# Phase_5.net
KiCad netlist of a schematic drawn in Altium Designer
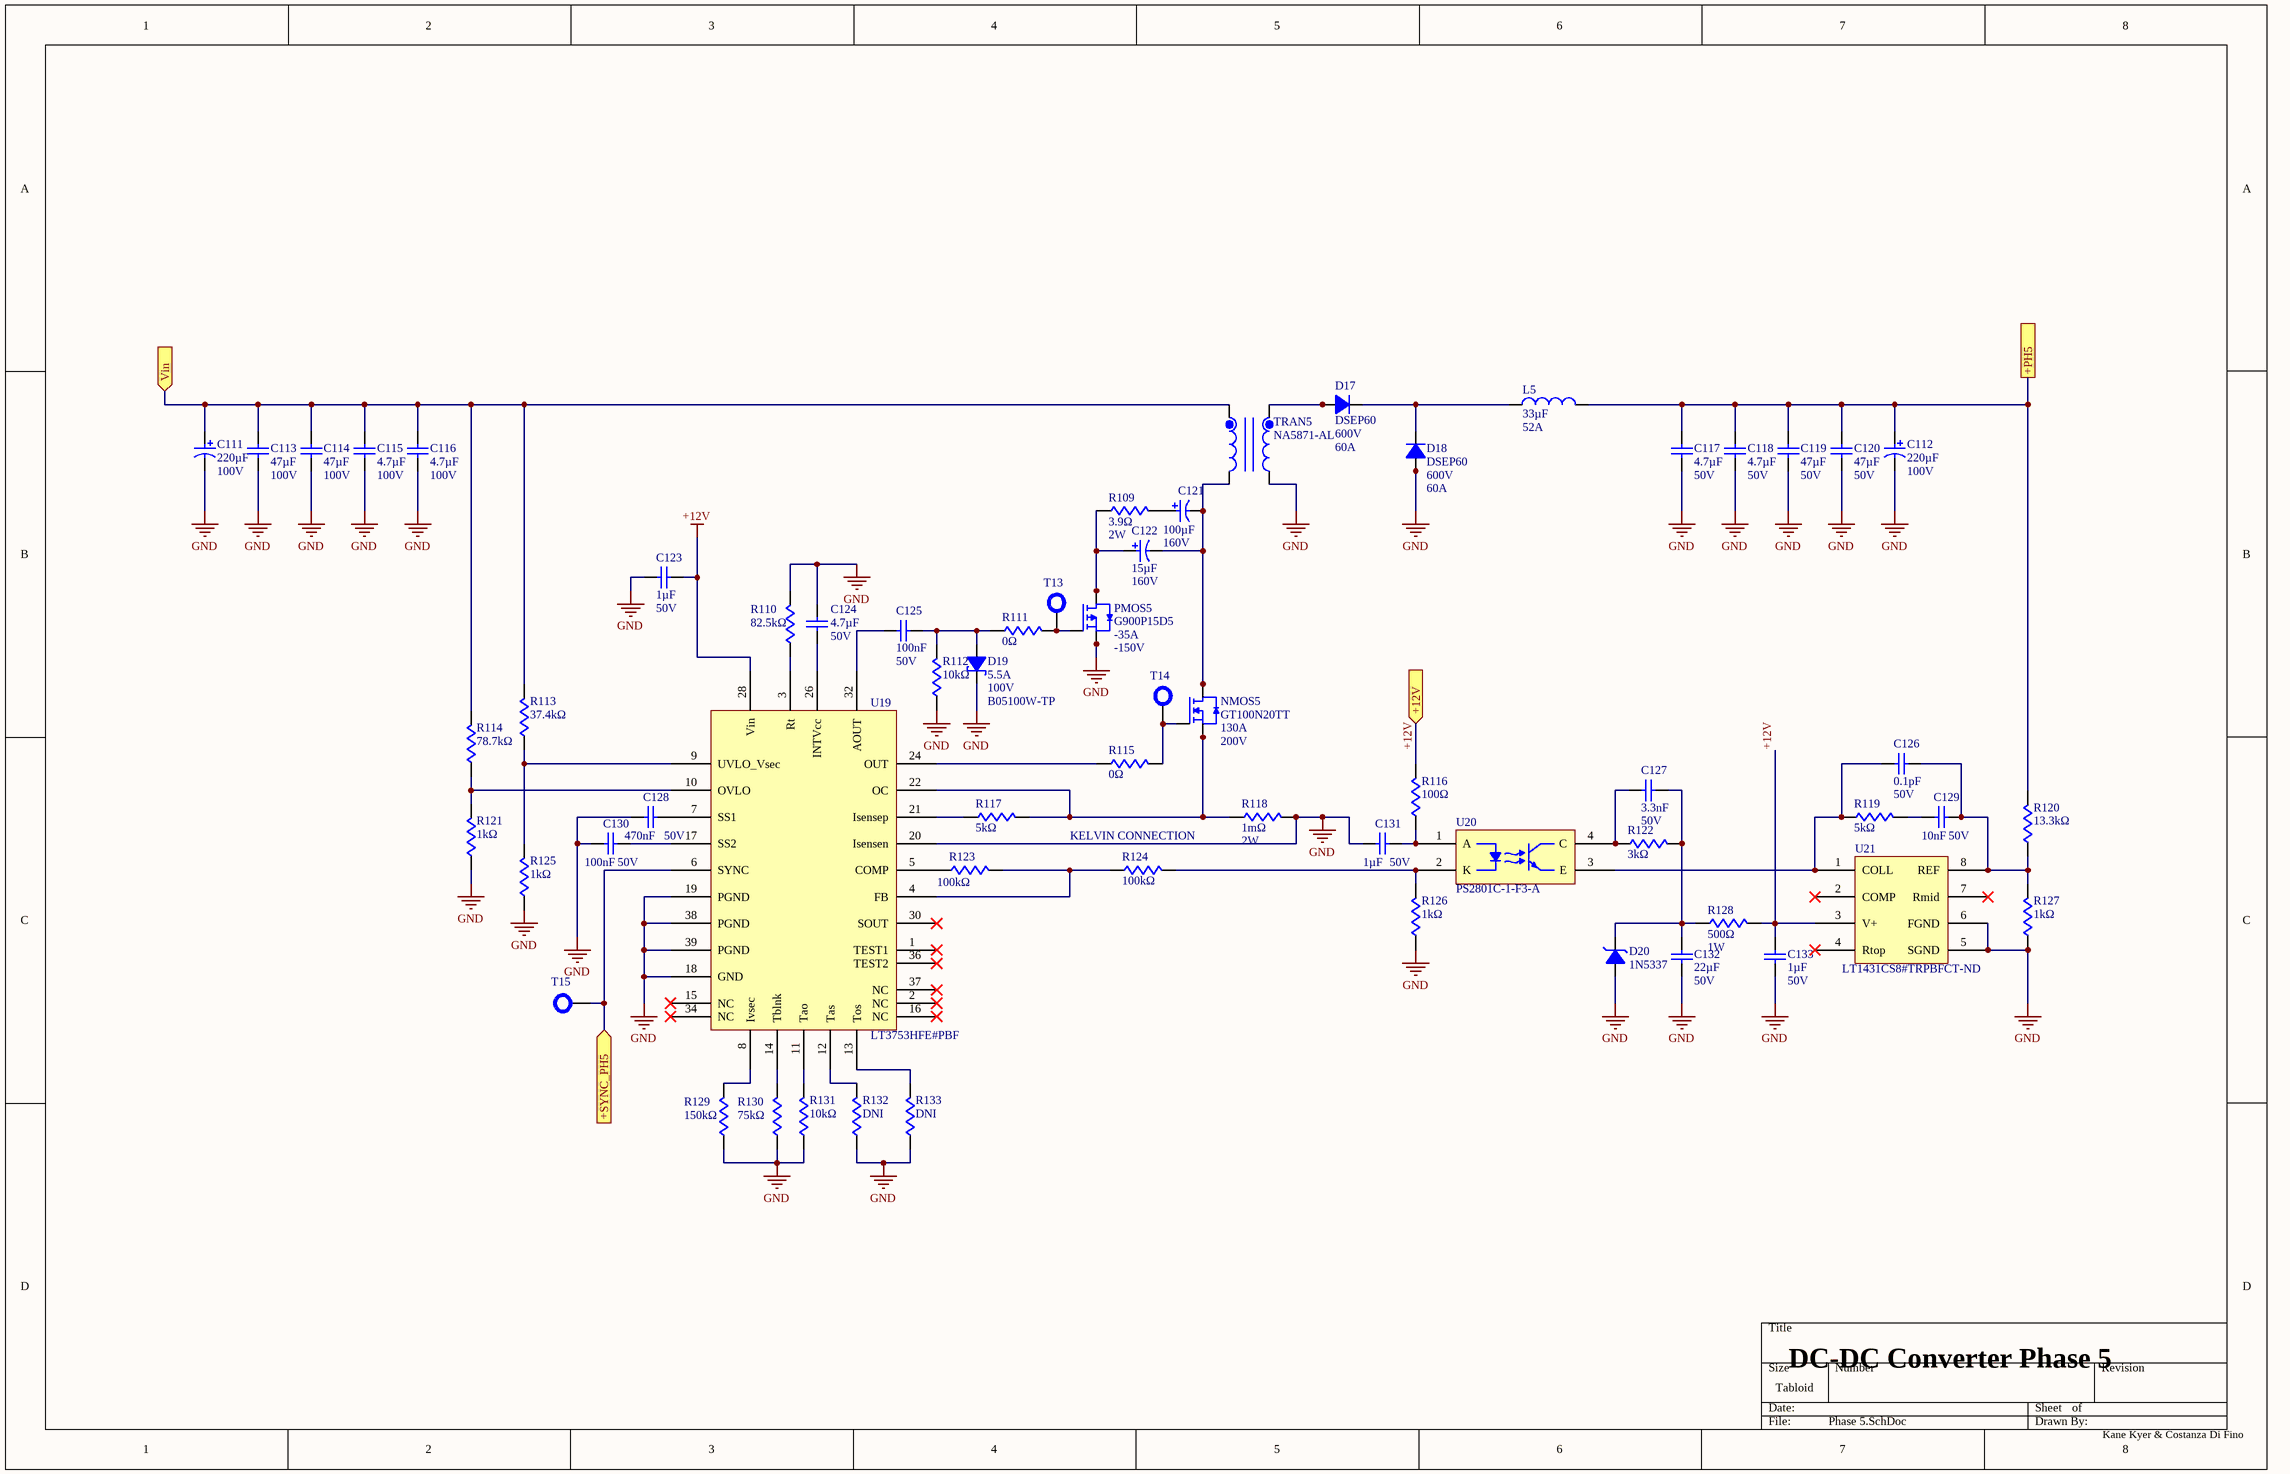
[diagram p0: Phase 5.SchDoc]

(export (version "E")
  (design (tool "Eeschema 10.0.6"))
  (components
    (comp (ref "C111")
      (value "220µF")
      (footprint "C_AEC")
      (description "Radial Can - SMD ALUMINUM ELECTROLYTIC CAPACITOR AFK 100V 220muF ±20% 0.709Dia 18.00mm")
      (fields
        (field (name "MANUFACTURER") "Cornell Dubilier")
        (field (name "MANUFACTURER PART NUMBER") "AFK227M2AR44T-F")
        (field (name "VOLTAGE RATING") "100V")
      )
      (libsource (lib "library") (part "AFK227M2AR44T-F"))
    )
    (comp (ref "C112")
      (value "220µF")
      (footprint "C_AEC")
      (description "Radial Can - SMD ALUMINUM ELECTROLYTIC CAPACITOR AFK 100V 220muF ±20% 0.709Dia 18.00mm")
      (fields
        (field (name "MANUFACTURER") "Cornell Dubilier")
        (field (name "MANUFACTURER PART NUMBER") "AFK227M2AR44T-F")
        (field (name "VOLTAGE RATING") "100V")
      )
      (libsource (lib "library") (part "AFK227M2AR44T-F"))
    )
    (comp (ref "C113")
      (value "47µF")
      (footprint "C_CAA573")
      (description "Multilayer Ceramic Chip Capacitors, Capacitance=47μF, LxWxT: 6.0x7.5x6.4mm")
      (fields
        (field (name "MANUFACTURER") "TDK")
        (field (name "MANUFACTURER PART NUMBER") "CAA573X7S2A476M640LH")
        (field (name "VOLTAGE RATING") "100V")
      )
      (libsource (lib "library") (part "CAA573X7S2A476M640LH"))
    )
    (comp (ref "C114")
      (value "47µF")
      (footprint "C_CAA573")
      (description "Multilayer Ceramic Chip Capacitors, Capacitance=47μF, LxWxT: 6.0x7.5x6.4mm")
      (fields
        (field (name "MANUFACTURER") "TDK")
        (field (name "MANUFACTURER PART NUMBER") "CAA573X7S2A476M640LH")
        (field (name "VOLTAGE RATING") "100V")
      )
      (libsource (lib "library") (part "CAA573X7S2A476M640LH"))
    )
    (comp (ref "C115")
      (value "4.7µF")
      (footprint "C_1210")
      (fields
        (field (name "MANUFACTURER") "Cal-Chip Electronics")
        (field (name "MANUFACTURER PART NUMBER") "GMC32X7S475K100NT")
        (field (name "VOLTAGE RATING (DC)") "100V")
      )
      (libsource (lib "library") (part "GMC32X7S475K100NT"))
    )
    (comp (ref "C116")
      (value "4.7µF")
      (footprint "C_1210")
      (fields
        (field (name "MANUFACTURER") "Cal-Chip Electronics")
        (field (name "MANUFACTURER PART NUMBER") "GMC32X7S475K100NT")
        (field (name "VOLTAGE RATING (DC)") "100V")
      )
      (libsource (lib "library") (part "GMC32X7S475K100NT"))
    )
    (comp (ref "C117")
      (value "4.7µF")
      (footprint "C_1206")
      (fields
        (field (name "MANUFACTURER") "Cal-Chip Electronics")
        (field (name "MANUFACTURER PART NUMBER") "GMC31X7R475K50NT")
        (field (name "VOLTAGE RATING (DC)") "50V")
      )
      (libsource (lib "library") (part "GMC31X7R475K50NT"))
    )
    (comp (ref "C118")
      (value "4.7µF")
      (footprint "C_1206")
      (fields
        (field (name "MANUFACTURER") "Cal-Chip Electronics")
        (field (name "MANUFACTURER PART NUMBER") "GMC31X7R475K50NT")
        (field (name "VOLTAGE RATING (DC)") "50V")
      )
      (libsource (lib "library") (part "GMC31X7R475K50NT"))
    )
    (comp (ref "C119")
      (value "47µF")
      (footprint "C_CKG57N")
      (fields
        (field (name "MANUFACTURER") "TDK")
        (field (name "MANUFACTURER PART NUMBER") "CKG57NX7R1H476M500JJ")
        (field (name "VOLTAGE RATING (DC)") "50V")
      )
      (libsource (lib "library") (part "CKG57NX7R1H476M500JJ"))
    )
    (comp (ref "C120")
      (value "47µF")
      (footprint "C_CKG57N")
      (fields
        (field (name "MANUFACTURER") "TDK")
        (field (name "MANUFACTURER PART NUMBER") "CKG57NX7R1H476M500JJ")
        (field (name "VOLTAGE RATING (DC)") "50V")
      )
      (libsource (lib "library") (part "CKG57NX7R1H476M500JJ"))
    )
    (comp (ref "C121")
      (value "100µF")
      (footprint "UUJ2C101MNJ1MS")
      (description "Aluminum Electrolytic Capacitors 100 F 160 V Radial, SMD 5000 Hrs 105C")
      (fields
        (field (name "MANUFACTURER") "Nichicon")
        (field (name "MANUFACTURER PART NUMBER") "UUJ2C101MNJ1MS")
        (field (name "VOLTAGE RATING (DC)") "160V")
      )
      (libsource (lib "library") (part "UUJ2C101MNJ1MS"))
    )
    (comp (ref "C122")
      (value "15µF")
      (footprint "ULT2C150MNL1GS")
      (description "Radial Can - SMD ALUMINUM ELECTROLYTIC CAPACITOR ULT 160V 15muF ±20% 0.315Dia 8.00mm")
      (fields
        (field (name "MANUFACTURER") "Nichicon")
        (field (name "MANUFACTURER PART NUMBER") "ULT2C150MNL1GS")
        (field (name "VOLTAGE") "160V")
      )
      (libsource (lib "library") (part "ULT2C150MNL1GS"))
    )
    (comp (ref "C123")
      (value "1µF")
      (footprint "C_0805")
      (description "50V 1uF X7R ±10% 0805 Multilayer Ceramic Capacitors MLCC - SMD/SMT ROHS")
      (fields
        (field (name "MANUFACTURER") "Samsung Electro-Mechanics")
        (field (name "MANUFACTURER PART NUMBER") "CL21B105KBFNNNE")
        (field (name "VOLTAGE") "50V")
      )
      (libsource (lib "library") (part "CL21B105KBFNNNE"))
    )
    (comp (ref "C124")
      (value "4.7µF")
      (footprint "C_1206")
      (fields
        (field (name "MANUFACTURER") "Cal-Chip Electronics")
        (field (name "MANUFACTURER PART NUMBER") "GMC31X7R475K50NT")
        (field (name "VOLTAGE RATING (DC)") "50V")
      )
      (libsource (lib "library") (part "GMC31X7R475K50NT"))
    )
    (comp (ref "C125")
      (value "100nF")
      (footprint "C_0603")
      (description "50V 100nF X7R ±10% 0603 Multilayer Ceramic Capacitors MLCC - SMD/SMT ROHS")
      (fields
        (field (name "MANUFACTURER") "KEMET")
        (field (name "MANUFACTURER PART NUMBER") "C0603C104K5RACTU")
        (field (name "VOLTAGE RATING") "50V")
      )
      (libsource (lib "library") (part "C0603C104K5RACTU"))
    )
    (comp (ref "C126")
      (value "0.1pF")
      (footprint "C_0402")
      (description "Multilayer Ceramic Capacitor, 0.1 pF, 50 V, ± 0.05pF, C0G (NP0), 0402 [1005 Metric]")
      (fields
        (field (name "MANUFACTURER") "Murata")
        (field (name "MANUFACTURER PART NUMBER") "GJM1555C1HR10WB01D")
        (field (name "VOLTAGE RATING") "50V")
      )
      (libsource (lib "library") (part "GJM1555C1HR10WB01D"))
    )
    (comp (ref "C127")
      (value "3.3nF")
      (footprint "C_0603")
      (description "50V 3.3nF C0G ±1% 0603 Multilayer Ceramic Capacitors MLCC - SMD/SMT ROHS")
      (fields
        (field (name "MANUFACTURER") "Murata")
        (field (name "MANUFACTURER PART NUMBER") "GCM1885C1H332FA16D")
        (field (name "VOLTAGE RATING") "50V")
      )
      (libsource (lib "library") (part "GCM1885C1H332FA16D"))
    )
    (comp (ref "C128")
      (value "470nF")
      (footprint "C_0402")
      (description "50V 470nF X5R ±10% 0402 Multilayer Ceramic Capacitors MLCC - SMD/SMT ROHS")
      (fields
        (field (name "MANUFACTURER") "Murata")
        (field (name "MANUFACTURER PART NUMBER") "GRM155R61H474KE11D")
        (field (name "VOLTAGE RATING") "50V")
      )
      (libsource (lib "library") (part "GRM155R61H474KE11D"))
    )
    (comp (ref "C129")
      (value "10nF")
      (footprint "C_0603")
      (description "Capacitor, Multilayer, Ceramic, 50V, 10%, X7R, 15% Tc, 0.01Uf, Surface Mount, 0603")
      (fields
        (field (name "MANUFACTURER") "KEMET")
        (field (name "MANUFACTURER PART NUMBER") "C0603C103K5RACTU")
        (field (name "VOLTAGE RATING") "50V")
      )
      (libsource (lib "library") (part "C0603C103K5RACTU"))
    )
    (comp (ref "C130")
      (value "100nF")
      (footprint "C_0603")
      (description "50V 100nF X7R ±10% 0603 Multilayer Ceramic Capacitors MLCC - SMD/SMT ROHS")
      (fields
        (field (name "MANUFACTURER") "KEMET")
        (field (name "MANUFACTURER PART NUMBER") "C0603C104K5RACTU")
        (field (name "VOLTAGE RATING") "50V")
      )
      (libsource (lib "library") (part "C0603C104K5RACTU"))
    )
    (comp (ref "C131")
      (value "1µF")
      (footprint "C_0805")
      (description "50V 1uF X7R ±10% 0805 Multilayer Ceramic Capacitors MLCC - SMD/SMT ROHS")
      (fields
        (field (name "MANUFACTURER") "Samsung Electro-Mechanics")
        (field (name "MANUFACTURER PART NUMBER") "CL21B105KBFNNNE")
        (field (name "VOLTAGE") "50V")
      )
      (libsource (lib "library") (part "CL21B105KBFNNNE"))
    )
    (comp (ref "C132")
      (value "22µF")
      (footprint "C_2220")
      (fields
        (field (name "MANUFACTURER") "Cal-Chip Electronics")
        (field (name "MANUFACTURER PART NUMBER") "GMC55X7R226M50NT")
        (field (name "VOLTAGE RATING (DC)") "50V")
      )
      (libsource (lib "library") (part "GMC55X7R226M50NT"))
    )
    (comp (ref "C133")
      (value "1µF")
      (footprint "C_0805")
      (description "50V 1uF X7R ±10% 0805 Multilayer Ceramic Capacitors MLCC - SMD/SMT ROHS")
      (fields
        (field (name "MANUFACTURER") "Samsung Electro-Mechanics")
        (field (name "MANUFACTURER PART NUMBER") "CL21B105KBFNNNE")
        (field (name "VOLTAGE") "50V")
      )
      (libsource (lib "library") (part "CL21B105KBFNNNE"))
    )
    (comp (ref "D17")
      (value "DSEP60")
      (footprint "D_DSEP60")
      (description "Power Diode Discretes-FRED TO-")
      (fields
        (field (name "MANUFACTURER") "IXYS")
        (field (name "MANUFACTURER PART NUMBER") "DSEP60-06AZ-TRL")
        (field (name "VR") "600V")
        (field (name "IO") "60A")
      )
      (libsource (lib "library") (part "DSEP60-06AZ-TRL"))
    )
    (comp (ref "D18")
      (value "DSEP60")
      (footprint "D_DSEP60")
      (description "Power Diode Discretes-FRED TO-")
      (fields
        (field (name "MANUFACTURER") "IXYS")
        (field (name "MANUFACTURER PART NUMBER") "DSEP60-06AZ-TRL")
        (field (name "VR") "600V")
        (field (name "IO") "60A")
      )
      (libsource (lib "library") (part "DSEP60-06AZ-TRL"))
    )
    (comp (ref "D19")
      (value "B05100W-TP")
      (footprint "D_B05100W")
      (description "Rectifier Diode, Schottky, 1 Phase, 1 Element, 0.5A, 100V V(RRM), Silicon")
      (fields
        (field (name "MANUFACTURER") "MCC")
        (field (name "MAX FORWARD SURGE CURRENT (IFSM)") "5.5A")
        (field (name "MIN BREAKDOWN VOLTAGE") "100V")
        (field (name "MANUFACTURER PART NUMBER") "B05100W-TP")
      )
      (libsource (lib "library") (part "B05100W-TP"))
    )
    (comp (ref "D20")
      (value "1N5337BRLG")
      (footprint "D_1N5337")
      (description "Zener Diode Single 4.7V 5% 2Ohm 5000mW 2-Pin Case 017AA-01 T/R / DIODE ZENER 4.7V 5W AXIAL")
      (fields
        (field (name "MANUFACTURER") "onsemi")
        (field (name "TOLERANCE") "5%")
        (field (name "SUPPLIER PART NUMBER") "1N5337")
      )
      (libsource (lib "library") (part "1N5337BRLG"))
    )
    (comp (ref "L5")
      (value "33µF")
      (footprint "CPEX4141L-330MC")
      (description "Fixed Ind 33UH 52A 1.88 Mohm Th")
      (fields
        (field (name "MANUFACTURER") "Codaca")
        (field (name "MANUFACTURER PART NUMBER") "CPEX4141L-330MC")
        (field (name "IRMS") "52A")
      )
      (libsource (lib "library") (part "CPEX4141L-330MC"))
    )
    (comp (ref "NMOS5")
      (value "GT100N20TT")
      (footprint "GT100N20TT")
      (description "Mosfet N-ch 200V 130A 280W Tolt")
      (fields
        (field (name "MANUFACTURER") "GoFord")
        (field (name "MANUFACTURER PART NUMBER") "GT100N20TT")
        (field (name "ID") "130A")
        (field (name "VDS") "200V")
      )
      (libsource (lib "library") (part "GT100N20TT"))
    )
    (comp (ref "PMOS5")
      (value "G900P15D5")
      (footprint "G900P15")
      (description "P-150V, -60A, RD(max) Less Than 80mOhm at -10V, VTH -1V to -4V, DFN5x6-8L")
      (fields
        (field (name "MANUFACTURER") "GoFord")
        (field (name "MANUFACTURER PART NUMBER") "G900P15D5")
        (field (name "ID") "-35A")
        (field (name "VDS") "-150V")
      )
      (libsource (lib "library") (part "G900P15D5"))
    )
    (comp (ref "R109")
      (value "3.9Ω")
      (footprint "R_SM2W")
      (description "SM Series 3.9 Ohm ±5 % 2 W ±200 ppm/°C Surface Mount Wirewound Resistor")
      (fields
        (field (name "MANUFACTURER") "TE Connectivity")
        (field (name "MANUFACTURER PART NUMBER") "SMW23R9JT")
        (field (name "POWER RATING") "2W")
      )
      (libsource (lib "library") (part "SMW23R9JT"))
    )
    (comp (ref "R110")
      (value "82.5kΩ")
      (footprint "R_0805")
      (description "Res Thick Film 0805 82.5K Ohm 1% 1/8W ±100ppm/°C Molded SMD SMD Paper T/R")
      (fields
        (field (name "MANUFACTURER") "Stackpole Electronics")
        (field (name "MANUFACTURER PART NUMBER") "RMCF0805FT82K5")
      )
      (libsource (lib "library") (part "RMCF0805FT82K5"))
    )
    (comp (ref "R111")
      (value "0Ω")
      (footprint "R_0805")
      (description "Zero Ohm Resistor, Jumper, 0805 [2012 Metric], Thick Film, 125 mW, 2.5 A, Surface Mount Device")
      (fields
        (field (name "MANUFACTURER") "Vishay")
        (field (name "MANUFACTURER PART NUMBER") "CRCW08050000Z0EA")
      )
      (libsource (lib "library") (part "CRCW08050000Z0EA"))
    )
    (comp (ref "R112")
      (value "10kΩ")
      (footprint "R_0402")
      (description "Fixed Resistor, Metal Glaze/thick Film, 0.0625W, 10000ohm, 50V, 1% +/-Tol, Surface Mount, 0402")
      (fields
        (field (name "MANUFACTURER") "Cal-Chip Electronics")
        (field (name "MANUFACTURER PART NUMBER") "RM04F1002CT")
      )
      (libsource (lib "library") (part "RM04F1002CT"))
    )
    (comp (ref "R113")
      (value "37.4kΩ")
      (footprint "R_0603")
      (description "100mW Thick Film Resistors 75V ±100ppm/℃ ±1% 37.4kΩ 0603 Chip Resistor - Surface Mount ROHS")
      (fields
        (field (name "MANUFACTURER") "Yageo Group")
        (field (name "MANUFACTURER PART NUMBER") "RC0603FR-0737K4L")
      )
      (libsource (lib "library") (part "RC0603FR-0737K4L"))
    )
    (comp (ref "R114")
      (value "78.7kΩ")
      (footprint "R_0603")
      (description "Res Thick Film 0603 78.7K Ohm 1% 0.1W(1/10W) ±100ppm/C Pad SMD T/R")
      (fields
        (field (name "MANUFACTURER") "Yageo Group")
        (field (name "MANUFACTURER PART NUMBER") "RC0603FR-0778K7L")
      )
      (libsource (lib "library") (part "RC0603FR-0778K7L"))
    )
    (comp (ref "R115")
      (value "0Ω")
      (footprint "R_0805")
      (description "Zero Ohm Resistor, Jumper, 0805 [2012 Metric], Thick Film, 125 mW, 2.5 A, Surface Mount Device")
      (fields
        (field (name "MANUFACTURER") "Vishay")
        (field (name "MANUFACTURER PART NUMBER") "CRCW08050000Z0EA")
      )
      (libsource (lib "library") (part "CRCW08050000Z0EA"))
    )
    (comp (ref "R116")
      (value "100Ω")
      (footprint "R_0603")
      (description "Yageo RC0603FR-07100RL 0603 SMD Resistor 100 Ohm thin film chip resistor")
      (fields
        (field (name "MANUFACTURER") "Yageo Group")
        (field (name "MANUFACTURER PART NUMBER") "RC0603FR-07100RL")
      )
      (libsource (lib "library") (part "RC0603FR-07100RL"))
    )
    (comp (ref "R117")
      (value "5kΩ")
      (footprint "R_0402")
      (description "Res Thin Film 0402 5K Ohm 0.1% 0.05W(1/20W) +/-25ppm/C Sulfur Resistant Pad SMD Medical T/R")
      (fields
        (field (name "MANUFACTURER") "Vishay")
        (field (name "MANUFACTURER PART NUMBER") "PNM0402E5001BST1")
      )
      (libsource (lib "library") (part "PNM0402E5001BST1"))
    )
    (comp (ref "R118")
      (value "1mΩ")
      (footprint "R_2512")
      (description "Res Thick Film 2512 1m Ohm 1% 2W ±75ppm/°C Molded SMD Embossed T/R")
      (fields
        (field (name "MANUFACTURER") "Bourns")
        (field (name "MANUFACTURER PART NUMBER") "CRE2512-FZ-R001E-2")
        (field (name "POWER RATING") "2W")
      )
      (libsource (lib "library") (part "CRE2512-FZ-R001E-2"))
    )
    (comp (ref "R119")
      (value "5kΩ")
      (footprint "R_0402")
      (description "Res Thin Film 0402 5K Ohm 0.1% 0.05W(1/20W) +/-25ppm/C Sulfur Resistant Pad SMD Medical T/R")
      (fields
        (field (name "MANUFACTURER") "Vishay")
        (field (name "MANUFACTURER PART NUMBER") "PNM0402E5001BST1")
      )
      (libsource (lib "library") (part "PNM0402E5001BST1"))
    )
    (comp (ref "R120")
      (value "13.3kΩ")
      (footprint "R_0603")
      (description "Res Thick Film 0603 13.3K Ohm 1% 0.1W(1/10W) ±100ppm/C Pad SMD Automotive T/R")
      (fields
        (field (name "MANUFACTURER") "Stackpole Electronics")
        (field (name "MANUFACTURER PART NUMBER") "RMCF0603FT13K3")
      )
      (libsource (lib "library") (part "RMCF0603FT13K3"))
    )
    (comp (ref "R121")
      (value "1kΩ")
      (footprint "R_0402")
      (description "62.5mW Thick Film Resistors ±100ppm/℃ ±1% 1kΩ 0402 Chip Resistor - Surface Mount ROHS")
      (fields
        (field (name "MANUFACTURER") "Cal-Chip Electronics")
        (field (name "MANUFACTURER PART NUMBER") "RM04F1001CT")
      )
      (libsource (lib "library") (part "RM04F1001CT"))
    )
    (comp (ref "R122")
      (value "3kΩ")
      (footprint "C_0402")
      (description "Res Thick Film 0402 3K Ohm 1% 0.063W(1/16W) ±100ppm/C Pad SMD Automotive T/R")
      (fields
        (field (name "MANUFACTURER") "Yageo Group")
        (field (name "MANUFACTURER PART NUMBER") "AC0402FR-073KL")
      )
      (libsource (lib "library") (part "AC0402FR-073KL"))
    )
    (comp (ref "R123")
      (value "100kΩ")
      (footprint "R_0402")
      (description "Fixed Resistor, Metal Glaze/thick Film, 0.0625W, 100000ohm, 50V, 1% +/-Tol, Surface Mount, 0402")
      (fields
        (field (name "MANUFACTURER") "Cal-Chip Electronics")
        (field (name "MANUFACTURER PART NUMBER") "RM04F1003CT")
      )
      (libsource (lib "library") (part "RM04F1003CT"))
    )
    (comp (ref "R124")
      (value "100kΩ")
      (footprint "R_0402")
      (description "Fixed Resistor, Metal Glaze/thick Film, 0.0625W, 100000ohm, 50V, 1% +/-Tol, Surface Mount, 0402")
      (fields
        (field (name "MANUFACTURER") "Cal-Chip Electronics")
        (field (name "MANUFACTURER PART NUMBER") "RM04F1003CT")
      )
      (libsource (lib "library") (part "RM04F1003CT"))
    )
    (comp (ref "R125")
      (value "1kΩ")
      (footprint "R_0402")
      (description "62.5mW Thick Film Resistors ±100ppm/℃ ±1% 1kΩ 0402 Chip Resistor - Surface Mount ROHS")
      (fields
        (field (name "MANUFACTURER") "Cal-Chip Electronics")
        (field (name "MANUFACTURER PART NUMBER") "RM04F1001CT")
      )
      (libsource (lib "library") (part "RM04F1001CT"))
    )
    (comp (ref "R126")
      (value "1kΩ")
      (footprint "R_0402")
      (description "62.5mW Thick Film Resistors ±100ppm/℃ ±1% 1kΩ 0402 Chip Resistor - Surface Mount ROHS")
      (fields
        (field (name "MANUFACTURER") "Cal-Chip Electronics")
        (field (name "MANUFACTURER PART NUMBER") "RM04F1001CT")
      )
      (libsource (lib "library") (part "RM04F1001CT"))
    )
    (comp (ref "R127")
      (value "1kΩ")
      (footprint "R_0402")
      (description "62.5mW Thick Film Resistors ±100ppm/℃ ±1% 1kΩ 0402 Chip Resistor - Surface Mount ROHS")
      (fields
        (field (name "MANUFACTURER") "Cal-Chip Electronics")
        (field (name "MANUFACTURER PART NUMBER") "RM04F1001CT")
      )
      (libsource (lib "library") (part "RM04F1001CT"))
    )
    (comp (ref "R128")
      (value "500Ω")
      (footprint "R_WSC2515")
      (description "Fixed Resistor, Wire Wound, 1W, 500ohm, 22.3607V, 1% +/-Tol, 20ppm/Cel, Surface Mount, 2515")
      (fields
        (field (name "MANUFACTURER") "Vishay")
        (field (name "MANUFACTURER PART NUMBER") "WSC2515500R0FEB")
        (field (name "POWER RATING") "1W")
      )
      (libsource (lib "library") (part "WSC2515500R0FEB"))
    )
    (comp (ref "R129")
      (value "150kΩ")
      (footprint "R_0603")
      (description "100mW Thick Film Resistors 75V ±100ppm/℃ ±1% 150kΩ 0603 Chip Resistor - Surface Mount ROHS")
      (fields
        (field (name "MANUFACTURER") "Yageo Group")
        (field (name "MANUFACTURER PART NUMBER") "RC0603FR-07150KL")
      )
      (libsource (lib "library") (part "RC0603FR-07150KL"))
    )
    (comp (ref "R130")
      (value "75kΩ")
      (footprint "R_0603")
      (description "Res Thick Film 0603 75K Ohm 1% 0.1W(1/10W) ±100ppm/C Pad SMD T/R Automotive AEC-Q200")
      (fields
        (field (name "MANUFACTURER") "Yageo Group")
        (field (name "MANUFACTURER PART NUMBER") "AC0603FR-0775KL")
      )
      (libsource (lib "library") (part "AC0603FR-0775KL"))
    )
    (comp (ref "R131")
      (value "10kΩ")
      (footprint "R_0402")
      (description "Fixed Resistor, Metal Glaze/thick Film, 0.0625W, 10000ohm, 50V, 1% +/-Tol, Surface Mount, 0402")
      (fields
        (field (name "MANUFACTURER") "Cal-Chip Electronics")
        (field (name "MANUFACTURER PART NUMBER") "RM04F1002CT")
      )
      (libsource (lib "library") (part "RM04F1002CT"))
    )
    (comp (ref "R132")
      (value "DNI")
      (footprint "R_0805")
      (description "Zero Ohm Resistor, Jumper, 0805 [2012 Metric], Thick Film, 125 mW, 2.5 A, Surface Mount Device")
      (fields
        (field (name "MANUFACTURER") "Vishay")
        (field (name "MANUFACTURER PART NUMBER") "CRCW08050000Z0EA")
      )
      (libsource (lib "library") (part "CRCW08050000Z0EA"))
    )
    (comp (ref "R133")
      (value "DNI")
      (footprint "R_0805")
      (description "Zero Ohm Resistor, Jumper, 0805 [2012 Metric], Thick Film, 125 mW, 2.5 A, Surface Mount Device")
      (fields
        (field (name "MANUFACTURER") "Vishay")
        (field (name "MANUFACTURER PART NUMBER") "CRCW08050000Z0EA")
      )
      (libsource (lib "library") (part "CRCW08050000Z0EA"))
    )
    (comp (ref "T13") (value "TEST") (footprint "TEST_POINT") (libsource (lib "library") (part "TEST")))
    (comp (ref "T14") (value "TEST") (footprint "TEST_POINT") (libsource (lib "library") (part "TEST")))
    (comp (ref "T15") (value "TEST") (footprint "TEST_POINT") (libsource (lib "library") (part "TEST")))
    (comp (ref "TRAN5")
      (value "NA5871-AL")
      (footprint "NA5871-AL")
      (description "Transformer, planar, for TI UCC28950, SMT, RoHS")
      (fields (field (name "MANUFACTURER") "Coilcraft") (field (name "SUPPLIER PART NUMBER") "NA5871-AL"))
      (libsource (lib "library") (part "NA5871-AL"))
    )
    (comp (ref "U19")
      (value "LT3753HFE#PBF")
      (footprint "LT3753")
      (description "500kHz 8.5V~100V Buck-boost type 1 TSSOP-38-EP-4.4mm DC-DC Controllers ROHS")
      (fields
        (field (name "MANUFACTURER") "Analog Devices")
        (field (name "MANUFACTURER PART NUMBER") "LT3753HFE#PBF")
      )
      (libsource (lib "library") (part "LT3753HFE#PBF"))
    )
    (comp (ref "U20")
      (value "PS2801C-1-F3-A")
      (footprint "PS2801C")
      (description "Optocoupler DC-IN 1-CH Transistor DC-OUT 4-Pin SSOP T/R")
      (fields
        (field (name "MANUFACTURER") "Renesas")
        (field (name "MANUFACTURER PART NUMBER") "PS2801C-1-F3-A")
      )
      (libsource (lib "library") (part "PS2801C-1-F3-A"))
    )
    (comp (ref "U21")
      (value "LT1431CS8#TRPBF")
      (footprint "LT1431")
      (description "V-Ref Adjustable 2.5V to 36V 100mA 8-Pin SOIC N T/R")
      (fields
        (field (name "SUPPLIER PART NUMBER") "LT1431CS8#TRPBFCT-ND")
        (field (name "MANUFACTURER") "Analog Devices")
        (field (name "TOLERANCE") "0.4%")
      )
      (libsource (lib "library") (part "LT1431CS8#TRPBF"))
    )
  )
  (nets
    (net (code "1") (name "+12V") (class "Default")
      (node (ref "C123") (pin "2") (pintype "passive"))
      (node (ref "C133") (pin "2") (pintype "passive"))
      (node (ref "R116") (pin "2") (pintype "passive"))
      (node (ref "R128") (pin "2") (pintype "passive"))
      (node (ref "U19") (pin "28") (pinfunction "Vin_28") (pintype "passive"))
      (node (ref "U21") (pin "3") (pinfunction "V+_3") (pintype "passive"))
    )
    (net (code "2") (name "/+PH5") (class "Default")
      (node (ref "C112") (pin "1") (pintype "passive"))
      (node (ref "C117") (pin "2") (pintype "passive"))
      (node (ref "C118") (pin "2") (pintype "passive"))
      (node (ref "C119") (pin "2") (pintype "passive"))
      (node (ref "C120") (pin "2") (pintype "passive"))
      (node (ref "L5") (pin "2") (pintype "passive"))
      (node (ref "R120") (pin "2") (pintype "passive"))
    )
    (net (code "3") (name "/+SYNC_PH5") (class "Default")
      (node (ref "T15") (pin "1") (pinfunction "1_1") (pintype "passive"))
      (node (ref "U19") (pin "6") (pinfunction "SYNC_6") (pintype "passive"))
    )
    (net (code "4") (name "/Vin") (class "Default")
      (node (ref "C111") (pin "1") (pintype "passive"))
      (node (ref "C113") (pin "2") (pintype "passive"))
      (node (ref "C114") (pin "2") (pintype "passive"))
      (node (ref "C115") (pin "2") (pintype "passive"))
      (node (ref "C116") (pin "2") (pintype "passive"))
      (node (ref "R113") (pin "2") (pintype "passive"))
      (node (ref "R114") (pin "2") (pintype "passive"))
      (node (ref "TRAN5") (pin "1") (pintype "passive"))
    )
    (net (code "5") (name "GND") (class "Default")
      (node (ref "C111") (pin "2") (pintype "passive"))
      (node (ref "C112") (pin "2") (pintype "passive"))
      (node (ref "C113") (pin "1") (pintype "passive"))
      (node (ref "C114") (pin "1") (pintype "passive"))
      (node (ref "C115") (pin "1") (pintype "passive"))
      (node (ref "C116") (pin "1") (pintype "passive"))
      (node (ref "C117") (pin "1") (pintype "passive"))
      (node (ref "C118") (pin "1") (pintype "passive"))
      (node (ref "C119") (pin "1") (pintype "passive"))
      (node (ref "C120") (pin "1") (pintype "passive"))
      (node (ref "C123") (pin "1") (pintype "passive"))
      (node (ref "C124") (pin "1") (pintype "passive"))
      (node (ref "C128") (pin "1") (pintype "passive"))
      (node (ref "C130") (pin "1") (pintype "passive"))
      (node (ref "C131") (pin "1") (pintype "passive"))
      (node (ref "C132") (pin "1") (pintype "passive"))
      (node (ref "C133") (pin "1") (pintype "passive"))
      (node (ref "D18") (pin "1") (pinfunction "A_1") (pintype "passive"))
      (node (ref "D18") (pin "3") (pinfunction "A_3") (pintype "passive"))
      (node (ref "D19") (pin "1") (pintype "passive"))
      (node (ref "D20") (pin "2") (pintype "passive"))
      (node (ref "PMOS5") (pin "1") (pinfunction "S_1") (pintype "passive"))
      (node (ref "PMOS5") (pin "2") (pinfunction "S_2") (pintype "passive"))
      (node (ref "PMOS5") (pin "3") (pinfunction "S_3") (pintype "passive"))
      (node (ref "R110") (pin "2") (pintype "passive"))
      (node (ref "R112") (pin "1") (pintype "passive"))
      (node (ref "R118") (pin "2") (pintype "passive"))
      (node (ref "R121") (pin "1") (pintype "passive"))
      (node (ref "R125") (pin "1") (pintype "passive"))
      (node (ref "R126") (pin "1") (pintype "passive"))
      (node (ref "R127") (pin "1") (pintype "passive"))
      (node (ref "R129") (pin "1") (pintype "passive"))
      (node (ref "R130") (pin "1") (pintype "passive"))
      (node (ref "R131") (pin "1") (pintype "passive"))
      (node (ref "R132") (pin "1") (pintype "passive"))
      (node (ref "R133") (pin "1") (pintype "passive"))
      (node (ref "TRAN5") (pin "11") (pintype "passive"))
      (node (ref "U19") (pin "18") (pinfunction "GND_18") (pintype "passive"))
      (node (ref "U19") (pin "19") (pinfunction "PGND_19") (pintype "passive"))
      (node (ref "U19") (pin "20") (pinfunction "Isensen_20") (pintype "passive"))
      (node (ref "U19") (pin "38") (pinfunction "PGND_38") (pintype "passive"))
      (node (ref "U19") (pin "39") (pinfunction "PGND_39") (pintype "passive"))
      (node (ref "U21") (pin "5") (pinfunction "SGND_5") (pintype "passive"))
      (node (ref "U21") (pin "6") (pinfunction "FGND_6") (pintype "passive"))
    )
    (net (code "6") (name "Net-(C121-Pad1)") (class "Default")
      (node (ref "C121") (pin "1") (pintype "passive"))
      (node (ref "R109") (pin "2") (pintype "passive"))
    )
    (net (code "7") (name "Net-(C121-Pad2)") (class "Default")
      (node (ref "C121") (pin "2") (pintype "passive"))
      (node (ref "C122") (pin "2") (pintype "passive"))
      (node (ref "NMOS5") (pin "10") (pinfunction "D_10") (pintype "passive"))
      (node (ref "NMOS5") (pin "11") (pinfunction "D_11") (pintype "passive"))
      (node (ref "NMOS5") (pin "12") (pinfunction "D_12") (pintype "passive"))
      (node (ref "NMOS5") (pin "13") (pinfunction "D_13") (pintype "passive"))
      (node (ref "NMOS5") (pin "14") (pinfunction "D_14") (pintype "passive"))
      (node (ref "NMOS5") (pin "15") (pinfunction "D_15") (pintype "passive"))
      (node (ref "NMOS5") (pin "16") (pinfunction "D_16") (pintype "passive"))
      (node (ref "NMOS5") (pin "9") (pinfunction "D_9") (pintype "passive"))
      (node (ref "TRAN5") (pin "4") (pintype "passive"))
    )
    (net (code "8") (name "Net-(C122-Pad1)") (class "Default")
      (node (ref "C122") (pin "1") (pintype "passive"))
      (node (ref "PMOS5") (pin "5") (pinfunction "D_5") (pintype "passive"))
      (node (ref "PMOS5") (pin "6") (pinfunction "D_6") (pintype "passive"))
      (node (ref "PMOS5") (pin "7") (pinfunction "D_7") (pintype "passive"))
      (node (ref "PMOS5") (pin "8") (pinfunction "D_8") (pintype "passive"))
      (node (ref "R109") (pin "1") (pintype "passive"))
    )
    (net (code "9") (name "Net-(C125-Pad2)") (class "Default")
      (node (ref "C125") (pin "2") (pintype "passive"))
      (node (ref "D19") (pin "2") (pintype "passive"))
      (node (ref "R111") (pin "1") (pintype "passive"))
      (node (ref "R112") (pin "2") (pintype "passive"))
    )
    (net (code "10") (name "Net-(C127-Pad2)") (class "Default")
      (node (ref "C127") (pin "2") (pintype "passive"))
      (node (ref "C132") (pin "2") (pintype "passive"))
      (node (ref "D20") (pin "1") (pintype "passive"))
      (node (ref "R122") (pin "2") (pintype "passive"))
      (node (ref "R128") (pin "1") (pintype "passive"))
    )
    (net (code "11") (name "Net-(C129-Pad1)") (class "Default")
      (node (ref "C129") (pin "1") (pintype "passive"))
      (node (ref "R119") (pin "2") (pintype "passive"))
    )
    (net (code "12") (name "Net-(D17-A-Pad1)") (class "Default")
      (node (ref "D17") (pin "1") (pinfunction "A_1") (pintype "passive"))
      (node (ref "D17") (pin "3") (pinfunction "A_3") (pintype "passive"))
      (node (ref "TRAN5") (pin "6") (pintype "passive"))
    )
    (net (code "13") (name "Net-(D17-C)") (class "Default")
      (node (ref "D17") (pin "4") (pinfunction "C_4") (pintype "passive"))
      (node (ref "D18") (pin "4") (pinfunction "C_4") (pintype "passive"))
      (node (ref "L5") (pin "1") (pintype "passive"))
    )
    (net (code "14") (name "Net-(NMOS5-G)") (class "Default")
      (node (ref "NMOS5") (pin "8") (pinfunction "G_8") (pintype "passive"))
      (node (ref "R115") (pin "2") (pintype "passive"))
      (node (ref "T14") (pin "1") (pinfunction "1_1") (pintype "passive"))
    )
    (net (code "15") (name "Net-(PMOS5-G)") (class "Default")
      (node (ref "PMOS5") (pin "4") (pinfunction "G_4") (pintype "passive"))
      (node (ref "R111") (pin "2") (pintype "passive"))
      (node (ref "T13") (pin "1") (pinfunction "1_1") (pintype "passive"))
    )
    (net (code "16") (name "Net-(U19-AOUT)") (class "Default")
      (node (ref "C125") (pin "1") (pintype "passive"))
      (node (ref "U19") (pin "32") (pinfunction "AOUT_32") (pintype "passive"))
    )
    (net (code "17") (name "Net-(U19-COMP)") (class "Default")
      (node (ref "R123") (pin "1") (pintype "passive"))
      (node (ref "U19") (pin "5") (pinfunction "COMP_5") (pintype "passive"))
    )
    (net (code "18") (name "Net-(U19-FB)") (class "Default")
      (node (ref "R123") (pin "2") (pintype "passive"))
      (node (ref "R124") (pin "1") (pintype "passive"))
      (node (ref "U19") (pin "4") (pinfunction "FB_4") (pintype "passive"))
    )
    (net (code "19") (name "Net-(U19-INTVcc)") (class "Default")
      (node (ref "C124") (pin "2") (pintype "passive"))
      (node (ref "U19") (pin "26") (pinfunction "INTVcc_26") (pintype "passive"))
    )
    (net (code "20") (name "Net-(U19-Isensep)") (class "Default")
      (node (ref "R117") (pin "1") (pintype "passive"))
      (node (ref "U19") (pin "21") (pinfunction "Isensep_21") (pintype "passive"))
    )
    (net (code "21") (name "Net-(U19-Ivsec)") (class "Default")
      (node (ref "R129") (pin "2") (pintype "passive"))
      (node (ref "U19") (pin "8") (pinfunction "Ivsec_8") (pintype "passive"))
    )
    (net (code "22") (name "Net-(U19-OC)") (class "Default")
      (node (ref "NMOS5") (pin "1") (pinfunction "S_1") (pintype "passive"))
      (node (ref "NMOS5") (pin "2") (pinfunction "S_2") (pintype "passive"))
      (node (ref "NMOS5") (pin "3") (pinfunction "S_3") (pintype "passive"))
      (node (ref "NMOS5") (pin "4") (pinfunction "S_4") (pintype "passive"))
      (node (ref "NMOS5") (pin "5") (pinfunction "S_5") (pintype "passive"))
      (node (ref "NMOS5") (pin "6") (pinfunction "S_6") (pintype "passive"))
      (node (ref "NMOS5") (pin "7") (pinfunction "S_7") (pintype "passive"))
      (node (ref "R117") (pin "2") (pintype "passive"))
      (node (ref "R118") (pin "1") (pintype "passive"))
      (node (ref "U19") (pin "22") (pinfunction "OC_22") (pintype "passive"))
    )
    (net (code "23") (name "Net-(U19-OUT)") (class "Default")
      (node (ref "R115") (pin "1") (pintype "passive"))
      (node (ref "U19") (pin "24") (pinfunction "OUT_24") (pintype "passive"))
    )
    (net (code "24") (name "Net-(U19-OVLO)") (class "Default")
      (node (ref "R114") (pin "1") (pintype "passive"))
      (node (ref "R121") (pin "2") (pintype "passive"))
      (node (ref "U19") (pin "10") (pinfunction "OVLO_10") (pintype "passive"))
    )
    (net (code "25") (name "Net-(U19-Rt)") (class "Default")
      (node (ref "R110") (pin "1") (pintype "passive"))
      (node (ref "U19") (pin "3") (pinfunction "Rt_3") (pintype "passive"))
    )
    (net (code "26") (name "Net-(U19-SS1)") (class "Default")
      (node (ref "C128") (pin "2") (pintype "passive"))
      (node (ref "U19") (pin "7") (pinfunction "SS1_7") (pintype "passive"))
    )
    (net (code "27") (name "Net-(U19-SS2)") (class "Default")
      (node (ref "C130") (pin "2") (pintype "passive"))
      (node (ref "U19") (pin "17") (pinfunction "SS2_17") (pintype "passive"))
    )
    (net (code "28") (name "Net-(U19-Tao)") (class "Default")
      (node (ref "R131") (pin "2") (pintype "passive"))
      (node (ref "U19") (pin "11") (pinfunction "Tao_11") (pintype "passive"))
    )
    (net (code "29") (name "Net-(U19-Tas)") (class "Default")
      (node (ref "R132") (pin "2") (pintype "passive"))
      (node (ref "U19") (pin "12") (pinfunction "Tas_12") (pintype "passive"))
    )
    (net (code "30") (name "Net-(U19-Tblnk)") (class "Default")
      (node (ref "R130") (pin "2") (pintype "passive"))
      (node (ref "U19") (pin "14") (pinfunction "Tblnk_14") (pintype "passive"))
    )
    (net (code "31") (name "Net-(U19-Tos)") (class "Default")
      (node (ref "R133") (pin "2") (pintype "passive"))
      (node (ref "U19") (pin "13") (pinfunction "Tos_13") (pintype "passive"))
    )
    (net (code "32") (name "Net-(U19-UVLO_Vsec)") (class "Default")
      (node (ref "R113") (pin "1") (pintype "passive"))
      (node (ref "R125") (pin "2") (pintype "passive"))
      (node (ref "U19") (pin "9") (pinfunction "UVLO_Vsec_9") (pintype "passive"))
    )
    (net (code "33") (name "Net-(U20-A)") (class "Default")
      (node (ref "C131") (pin "2") (pintype "passive"))
      (node (ref "R116") (pin "1") (pintype "passive"))
      (node (ref "U20") (pin "1") (pinfunction "A_1") (pintype "passive"))
    )
    (net (code "34") (name "Net-(U20-C)") (class "Default")
      (node (ref "C127") (pin "1") (pintype "passive"))
      (node (ref "R122") (pin "1") (pintype "passive"))
      (node (ref "U20") (pin "4") (pinfunction "C_4") (pintype "passive"))
    )
    (net (code "35") (name "Net-(U20-E)") (class "Default")
      (node (ref "C126") (pin "1") (pintype "passive"))
      (node (ref "R119") (pin "1") (pintype "passive"))
      (node (ref "U20") (pin "3") (pinfunction "E_3") (pintype "passive"))
      (node (ref "U21") (pin "1") (pinfunction "COLL_1") (pintype "passive"))
    )
    (net (code "36") (name "Net-(U20-K)") (class "Default")
      (node (ref "R124") (pin "2") (pintype "passive"))
      (node (ref "R126") (pin "2") (pintype "passive"))
      (node (ref "U20") (pin "2") (pinfunction "K_2") (pintype "passive"))
    )
    (net (code "37") (name "Net-(U21-REF)") (class "Default")
      (node (ref "C126") (pin "2") (pintype "passive"))
      (node (ref "C129") (pin "2") (pintype "passive"))
      (node (ref "R120") (pin "1") (pintype "passive"))
      (node (ref "R127") (pin "2") (pintype "passive"))
      (node (ref "U21") (pin "8") (pinfunction "REF_8") (pintype "passive"))
    )
    (net (code "38") (name "unconnected-(U19-NC-Pad2)") (class "Default")
      (node (ref "U19") (pin "2") (pinfunction "NC_2") (pintype "passive+no_connect"))
    )
    (net (code "39") (name "unconnected-(U19-NC-Pad15)") (class "Default")
      (node (ref "U19") (pin "15") (pinfunction "NC_15") (pintype "passive+no_connect"))
    )
    (net (code "40") (name "unconnected-(U19-NC-Pad16)") (class "Default")
      (node (ref "U19") (pin "16") (pinfunction "NC_16") (pintype "passive+no_connect"))
    )
    (net (code "41") (name "unconnected-(U19-NC-Pad34)") (class "Default")
      (node (ref "U19") (pin "34") (pinfunction "NC_34") (pintype "passive+no_connect"))
    )
    (net (code "42") (name "unconnected-(U19-NC-Pad37)") (class "Default")
      (node (ref "U19") (pin "37") (pinfunction "NC_37") (pintype "passive+no_connect"))
    )
    (net (code "43") (name "unconnected-(U19-SOUT-Pad30)") (class "Default")
      (node (ref "U19") (pin "30") (pinfunction "SOUT_30") (pintype "passive+no_connect"))
    )
    (net (code "44") (name "unconnected-(U19-TEST1-Pad1)") (class "Default")
      (node (ref "U19") (pin "1") (pinfunction "TEST1_1") (pintype "passive+no_connect"))
    )
    (net (code "45") (name "unconnected-(U19-TEST2-Pad36)") (class "Default")
      (node (ref "U19") (pin "36") (pinfunction "TEST2_36") (pintype "passive+no_connect"))
    )
    (net (code "46") (name "unconnected-(U21-COMP-Pad2)") (class "Default")
      (node (ref "U21") (pin "2") (pinfunction "COMP_2") (pintype "passive+no_connect"))
    )
    (net (code "47") (name "unconnected-(U21-Rmid-Pad7)") (class "Default")
      (node (ref "U21") (pin "7") (pinfunction "Rmid_7") (pintype "passive+no_connect"))
    )
    (net (code "48") (name "unconnected-(U21-Rtop-Pad4)") (class "Default")
      (node (ref "U21") (pin "4") (pinfunction "Rtop_4") (pintype "passive+no_connect"))
    )
  )
)
